# JDM2_NoDIL.net
KiCad netlist of a schematic drawn in EAGLE
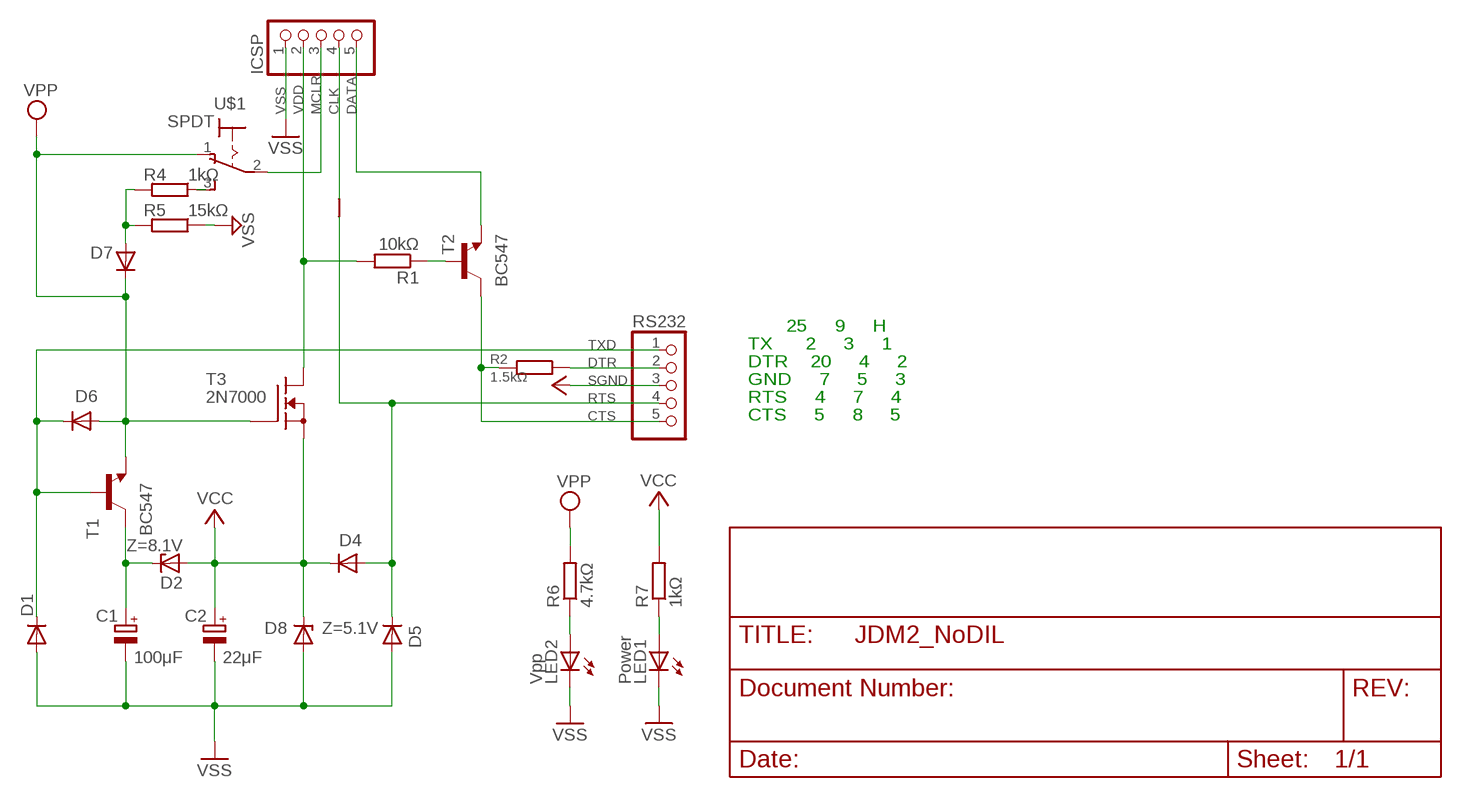
[diagram p0: schematic, sheet 1]

(export (version "E")
  (design (tool "Eeschema 10.0.6"))
  (components
    (comp (ref "C1")
      (value "100μF")
      (footprint "eagle-import:E2,5-5")
      (libsource (lib "eagle-import") (part "CPOL-EUE2.5-5"))
    )
    (comp (ref "C2")
      (value "22μF")
      (footprint "eagle-import:E2,5-5")
      (libsource (lib "eagle-import") (part "CPOL-EUE2.5-5"))
    )
    (comp (ref "D1")
      (value "1N4148")
      (footprint "eagle-import:DO35-5")
      (libsource (lib "eagle-import") (part "1N4148-5"))
    )
    (comp (ref "D2")
      (value "Z=8.1V")
      (footprint "eagle-import:DO35Z5")
      (libsource (lib "eagle-import") (part "Z-DIODEZ5"))
    )
    (comp (ref "D4")
      (value "1N4148")
      (footprint "eagle-import:DO35-2_54")
      (libsource (lib "eagle-import") (part "1N4148-2.54"))
    )
    (comp (ref "D5")
      (value "1N4148")
      (footprint "eagle-import:DO34-15")
      (libsource (lib "eagle-import") (part "1N4148-15"))
    )
    (comp (ref "D6")
      (value "1N4148")
      (footprint "eagle-import:DO35-5")
      (libsource (lib "eagle-import") (part "1N4148-5"))
    )
    (comp (ref "D7")
      (value "2N4148")
      (footprint "eagle-import:DO35-5")
      (libsource (lib "eagle-import") (part "1N4148-5"))
    )
    (comp (ref "D8")
      (value "Z=5.1V")
      (footprint "eagle-import:DO35Z10")
      (libsource (lib "eagle-import") (part "Z-DIODEZ10"))
    )
    (comp (ref "ICSP")
      (value "PINHD-1X5")
      (footprint "eagle-import:1X05")
      (libsource (lib "eagle-import") (part "PINHD-1X5"))
    )
    (comp (ref "J1")
      (value "DUMMY")
      (footprint "eagle-import:DUMMY")
      (libsource (lib "eagle-import") (part "DUMMY"))
    )
    (comp (ref "LED1")
      (value "Power")
      (footprint "eagle-import:LED5MM")
      (libsource (lib "eagle-import") (part "LED"))
    )
    (comp (ref "LED2")
      (value "Vpp")
      (footprint "eagle-import:LED5MM")
      (libsource (lib "eagle-import") (part "LED"))
    )
    (comp (ref "R1")
      (value "10kΩ")
      (footprint "eagle-import:0207_10")
      (libsource (lib "eagle-import") (part "RES-0207-10"))
    )
    (comp (ref "R2")
      (value "1.5kΩ")
      (footprint "eagle-import:0204_7")
      (libsource (lib "eagle-import") (part "RES-0204-7"))
    )
    (comp (ref "R4")
      (value "1kΩ")
      (footprint "eagle-import:0207_10")
      (libsource (lib "eagle-import") (part "RES-0207-10"))
    )
    (comp (ref "R5")
      (value "15kΩ")
      (footprint "eagle-import:0207_10")
      (libsource (lib "eagle-import") (part "RES-0207-10"))
    )
    (comp (ref "R6")
      (value "4.7kΩ")
      (footprint "eagle-import:0207_10")
      (libsource (lib "eagle-import") (part "RES-0207-10"))
    )
    (comp (ref "R7")
      (value "1kΩ")
      (footprint "eagle-import:0207_10")
      (libsource (lib "eagle-import") (part "RES-0207-10"))
    )
    (comp (ref "RS232")
      (value "PINHD-1X5")
      (footprint "eagle-import:1X05")
      (libsource (lib "eagle-import") (part "PINHD-1X5"))
    )
    (comp (ref "T1")
      (value "BC547")
      (footprint "eagle-import:TO92-CBE")
      (libsource (lib "eagle-import") (part "BC547"))
    )
    (comp (ref "T2")
      (value "BC547")
      (footprint "eagle-import:TO92-CBE")
      (libsource (lib "eagle-import") (part "BC547"))
    )
    (comp (ref "T3")
      (value "2N7000")
      (footprint "eagle-import:TO92")
      (libsource (lib "eagle-import") (part "2N7000"))
    )
    (comp (ref "U$1")
      (value "SPDT")
      (footprint "eagle-import:SPDT")
      (libsource (lib "eagle-import") (part "SPDT"))
    )
  )
  (nets
    (net (code "1") (name "/CLK") (class "Default")
      (node (ref "ICSP") (pin "4") (pinfunction "4_4") (pintype "passive"))
      (node (ref "J1") (pin "2") (pinfunction "2_2") (pintype "passive"))
    )
    (net (code "2") (name "/CTS") (class "Default")
      (node (ref "R2") (pin "2") (pinfunction "2_2") (pintype "passive"))
      (node (ref "RS232") (pin "5") (pinfunction "5_5") (pintype "passive"))
      (node (ref "T2") (pin "C") (pinfunction "C_C") (pintype "passive"))
    )
    (net (code "3") (name "/DATA") (class "Default")
      (node (ref "ICSP") (pin "5") (pinfunction "5_5") (pintype "passive"))
      (node (ref "T2") (pin "E") (pinfunction "E_E") (pintype "passive"))
    )
    (net (code "4") (name "/DTR") (class "Default")
      (node (ref "R2") (pin "1") (pinfunction "1_1") (pintype "passive"))
      (node (ref "RS232") (pin "2") (pinfunction "2_2") (pintype "passive"))
    )
    (net (code "5") (name "/MCLR") (class "Default")
      (node (ref "ICSP") (pin "3") (pinfunction "3_3") (pintype "passive"))
      (node (ref "U$1") (pin "2") (pinfunction "P_2") (pintype "passive"))
    )
    (net (code "6") (name "/RTS") (class "Default")
      (node (ref "D4") (pin "A") (pinfunction "A_A") (pintype "passive"))
      (node (ref "D5") (pin "C") (pinfunction "C_C") (pintype "passive"))
      (node (ref "J1") (pin "1") (pinfunction "1_1") (pintype "passive"))
      (node (ref "RS232") (pin "4") (pinfunction "4_4") (pintype "passive"))
    )
    (net (code "7") (name "/TXD") (class "Default")
      (node (ref "D1") (pin "C") (pinfunction "C_C") (pintype "passive"))
      (node (ref "D6") (pin "C") (pinfunction "C_C") (pintype "passive"))
      (node (ref "RS232") (pin "1") (pinfunction "1_1") (pintype "passive"))
      (node (ref "T1") (pin "B") (pinfunction "B_B") (pintype "passive"))
    )
    (net (code "8") (name "/VDD") (class "Default")
      (node (ref "ICSP") (pin "2") (pinfunction "2_2") (pintype "passive"))
      (node (ref "R1") (pin "2") (pinfunction "2_2") (pintype "passive"))
      (node (ref "T3") (pin "3") (pinfunction "D_3") (pintype "passive"))
    )
    (net (code "9") (name "Net-(C1-Pad+)") (class "Default")
      (node (ref "C1") (pin "+") (pinfunction "+_+") (pintype "passive"))
      (node (ref "D2") (pin "C") (pinfunction "C_C") (pintype "passive"))
      (node (ref "T1") (pin "C") (pinfunction "C_C") (pintype "passive"))
    )
    (net (code "10") (name "Net-(D7-PadA)") (class "Default")
      (node (ref "D7") (pin "A") (pinfunction "A_A") (pintype "passive"))
      (node (ref "R4") (pin "2") (pinfunction "2_2") (pintype "passive"))
      (node (ref "R5") (pin "2") (pinfunction "2_2") (pintype "passive"))
    )
    (net (code "11") (name "Net-(LED1-PadA)") (class "Default")
      (node (ref "LED1") (pin "A") (pinfunction "A_A") (pintype "passive"))
      (node (ref "R7") (pin "1") (pinfunction "1_1") (pintype "passive"))
    )
    (net (code "12") (name "Net-(LED2-PadA)") (class "Default")
      (node (ref "LED2") (pin "A") (pinfunction "A_A") (pintype "passive"))
      (node (ref "R6") (pin "1") (pinfunction "1_1") (pintype "passive"))
    )
    (net (code "13") (name "Net-(R1-Pad1)") (class "Default")
      (node (ref "R1") (pin "1") (pinfunction "1_1") (pintype "passive"))
      (node (ref "T2") (pin "B") (pinfunction "B_B") (pintype "passive"))
    )
    (net (code "14") (name "Net-(U$1-S)") (class "Default")
      (node (ref "R4") (pin "1") (pinfunction "1_1") (pintype "passive"))
      (node (ref "U$1") (pin "3") (pinfunction "S_3") (pintype "passive"))
    )
    (net (code "15") (name "VCC") (class "Default")
      (node (ref "C2") (pin "+") (pinfunction "+_+") (pintype "passive"))
      (node (ref "D2") (pin "A") (pinfunction "A_A") (pintype "passive"))
      (node (ref "D4") (pin "C") (pinfunction "C_C") (pintype "passive"))
      (node (ref "D8") (pin "C") (pinfunction "C_C") (pintype "passive"))
      (node (ref "R7") (pin "2") (pinfunction "2_2") (pintype "passive"))
      (node (ref "RS232") (pin "3") (pinfunction "3_3") (pintype "passive"))
      (node (ref "T3") (pin "1") (pinfunction "S_1") (pintype "passive"))
    )
    (net (code "16") (name "VPP") (class "Default")
      (node (ref "D6") (pin "A") (pinfunction "A_A") (pintype "passive"))
      (node (ref "D7") (pin "C") (pinfunction "C_C") (pintype "passive"))
      (node (ref "R6") (pin "2") (pinfunction "2_2") (pintype "passive"))
      (node (ref "T1") (pin "E") (pinfunction "E_E") (pintype "passive"))
      (node (ref "T3") (pin "2") (pinfunction "G_2") (pintype "passive"))
      (node (ref "U$1") (pin "1") (pinfunction "O_1") (pintype "passive"))
    )
    (net (code "17") (name "VSS") (class "Default")
      (node (ref "C1") (pin "-") (pinfunction "-_-") (pintype "passive"))
      (node (ref "C2") (pin "-") (pinfunction "-_-") (pintype "passive"))
      (node (ref "D1") (pin "A") (pinfunction "A_A") (pintype "passive"))
      (node (ref "D5") (pin "A") (pinfunction "A_A") (pintype "passive"))
      (node (ref "D8") (pin "A") (pinfunction "A_A") (pintype "passive"))
      (node (ref "ICSP") (pin "1") (pinfunction "1_1") (pintype "passive"))
      (node (ref "LED1") (pin "K") (pinfunction "C_K") (pintype "passive"))
      (node (ref "LED2") (pin "K") (pinfunction "C_K") (pintype "passive"))
      (node (ref "R5") (pin "1") (pinfunction "1_1") (pintype "passive"))
    )
  )
)
